# M66_GPRS.net
KiCad netlist of a schematic drawn in Altium Designer
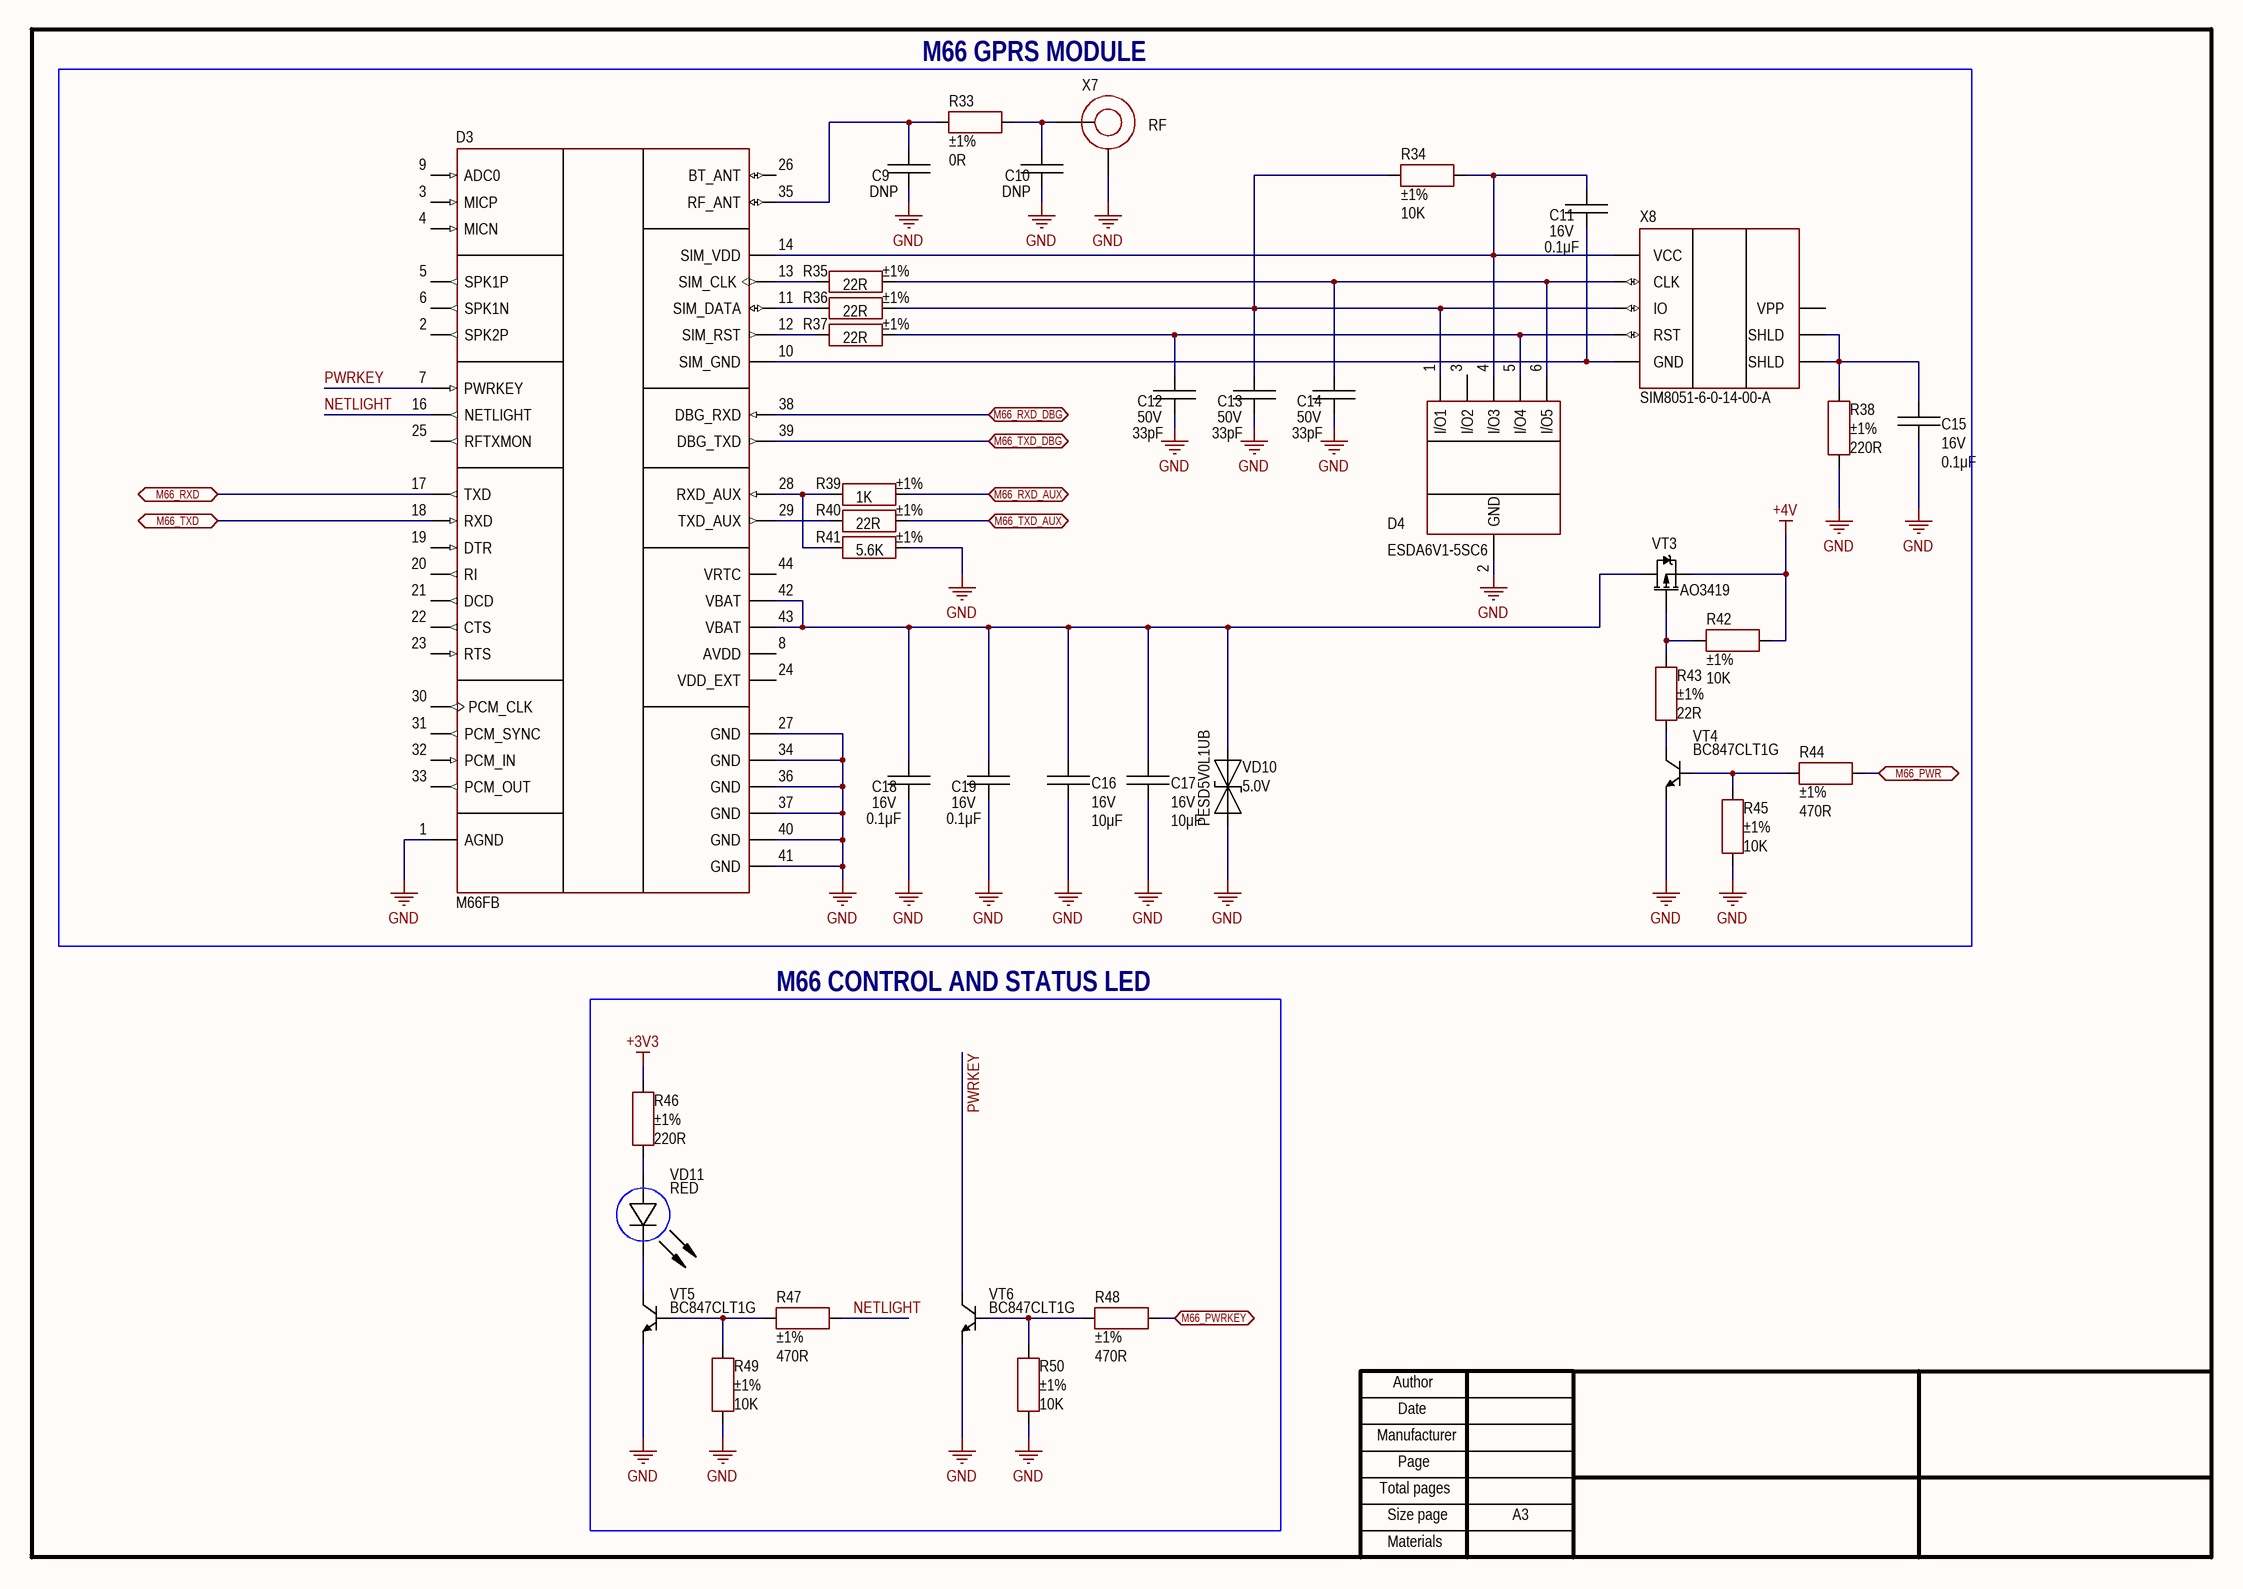
[diagram p0: M66_GPRS.SchDoc]

(export (version "E")
  (design (tool "Eeschema 10.0.6"))
  (components
    (comp (ref "C9")
      (value "DNP")
      (footprint "CAP: 0402")
      (libsource (lib "capacitor") (part "Ceramic_0402"))
    )
    (comp (ref "C10")
      (value "DNP")
      (footprint "CAP: 0402")
      (libsource (lib "capacitor") (part "Ceramic_0402"))
    )
    (comp (ref "C11")
      (value "0.1μF")
      (footprint "CAP: 0402")
      (description "±10% 16V Ceramic Capacitor X7R 0402 (1005 Metric)")
      (fields
        (field (name "MANUFACTURER") "Yageo")
        (field (name "PARTNUMBER") "CC0402KRX7R7BB104")
        (field (name "VOLTAGE") "16V")
      )
      (libsource (lib "capacitor") (part "Ceramic_0402"))
    )
    (comp (ref "C12")
      (value "33pF")
      (footprint "CAP: 0402")
      (description "33 pF ±5% 50V Ceramic Capacitor C0G, NP0 0402 (1005 Metric)")
      (fields
        (field (name "MANUFACTURER") "Yageo")
        (field (name "PARTNUMBER") "CC0402JRNPO9BN330")
        (field (name "VOLTAGE") "50V")
      )
      (libsource (lib "capacitor") (part "Ceramic_0402"))
    )
    (comp (ref "C13")
      (value "33pF")
      (footprint "CAP: 0402")
      (description "33 pF ±5% 50V Ceramic Capacitor C0G, NP0 0402 (1005 Metric)")
      (fields
        (field (name "MANUFACTURER") "Yageo")
        (field (name "PARTNUMBER") "CC0402JRNPO9BN330")
        (field (name "VOLTAGE") "50V")
      )
      (libsource (lib "capacitor") (part "Ceramic_0402"))
    )
    (comp (ref "C14")
      (value "33pF")
      (footprint "CAP: 0402")
      (description "33 pF ±5% 50V Ceramic Capacitor C0G, NP0 0402 (1005 Metric)")
      (fields
        (field (name "MANUFACTURER") "Yageo")
        (field (name "PARTNUMBER") "CC0402JRNPO9BN330")
        (field (name "VOLTAGE") "50V")
      )
      (libsource (lib "capacitor") (part "Ceramic_0402"))
    )
    (comp (ref "C15")
      (value "0.1μF")
      (footprint "CAP: 0402")
      (description "±10% 16V Ceramic Capacitor X7R 0402 (1005 Metric)")
      (fields
        (field (name "MANUFACTURER") "Yageo")
        (field (name "PARTNUMBER") "CC0402KRX7R7BB104")
        (field (name "VOLTAGE") "16V")
      )
      (libsource (lib "capacitor") (part "Ceramic_0402"))
    )
    (comp (ref "C16")
      (value "10μF")
      (footprint "CAP: 0805")
      (description "±20% 16V Ceramic Capacitor X7R 0805 (2012 Metric)")
      (fields
        (field (name "MANUFACTURER") "Yageo")
        (field (name "PARTNUMBER") "CC0805MKX7R7BB106")
        (field (name "VOLTAGE") "16V")
      )
      (libsource (lib "capacitor") (part "Ceramic_0805"))
    )
    (comp (ref "C17")
      (value "10μF")
      (footprint "CAP: 0805")
      (description "±20% 16V Ceramic Capacitor X7R 0805 (2012 Metric)")
      (fields
        (field (name "MANUFACTURER") "Yageo")
        (field (name "PARTNUMBER") "CC0805MKX7R7BB106")
        (field (name "VOLTAGE") "16V")
      )
      (libsource (lib "capacitor") (part "Ceramic_0805"))
    )
    (comp (ref "C18")
      (value "0.1μF")
      (footprint "CAP: 0402")
      (description "±10% 16V Ceramic Capacitor X7R 0402 (1005 Metric)")
      (fields
        (field (name "MANUFACTURER") "Yageo")
        (field (name "PARTNUMBER") "CC0402KRX7R7BB104")
        (field (name "VOLTAGE") "16V")
      )
      (libsource (lib "capacitor") (part "Ceramic_0402"))
    )
    (comp (ref "C19")
      (value "0.1μF")
      (footprint "CAP: 0402")
      (description "±10% 16V Ceramic Capacitor X7R 0402 (1005 Metric)")
      (fields
        (field (name "MANUFACTURER") "Yageo")
        (field (name "PARTNUMBER") "CC0402KRX7R7BB104")
        (field (name "VOLTAGE") "16V")
      )
      (libsource (lib "capacitor") (part "Ceramic_0402"))
    )
    (comp (ref "D3")
      (value "~")
      (footprint "MOD: M66")
      (description "GPRS Modem")
      (fields (field (name "MANUFACTURER") "Quectel") (field (name "PARTNUMBER") "M66FB"))
      (libsource (lib "MyLib") (part "M66FB"))
    )
    (comp (ref "D4")
      (value "~")
      (footprint "SOT23-6")
      (description "6.1V 100W TVS Array Surface Mount SOT-23-6")
      (fields
        (field (name "MANUFACTURER") "STMicroelectronics")
        (field (name "VALUEMANUFACTURERPARTNUMBER") "TVS array, , 5A peak, 6.1V, , SOT-23-6, -40...+125°C")
        (field (name "PARTNUMBER") "ESDA6V1-5SC6")
      )
      (libsource (lib "MyLib") (part "ESDA6V1-5SC6"))
    )
    (comp (ref "R33")
      (value "0R")
      (footprint "RES: 0402")
      (description "0 Ohms Jumper 0.063W, 1/16W Chip Resistor 0402 (1005 Metric) Moisture Resistant Thick Film")
      (fields
        (field (name "MANUFACTURER") "Yageo")
        (field (name "PARTNUMBER") "RC0402JR-070RL")
        (field (name "TOLERANCE") "±1%")
      )
      (libsource (lib "resistor") (part "Resistor_0402"))
    )
    (comp (ref "R34")
      (value "10K")
      (footprint "RES: 0402")
      (description "10 kOhms ±1% 0.063W, 1/16W Chip Resistor 0402 (1005 Metric) Moisture Resistant Thick Film")
      (fields
        (field (name "MANUFACTURER") "Yageo")
        (field (name "PARTNUMBER") "RC0402FR-0710KL")
        (field (name "TOLERANCE") "±1%")
      )
      (libsource (lib "resistor") (part "Resistor_0402"))
    )
    (comp (ref "R35")
      (value "22R")
      (footprint "RES: 0402")
      (description "22 Ohms ±1% 0.063W, 1/16W Chip Resistor 0402 (1005 Metric) Moisture Resistant Thick Film")
      (fields
        (field (name "MANUFACTURER") "Yageo")
        (field (name "PARTNUMBER") "RC0402FR-0722RL")
        (field (name "TOLERANCE") "±1%")
      )
      (libsource (lib "") (part "Resistor_0402_1"))
    )
    (comp (ref "R36")
      (value "22R")
      (footprint "RES: 0402")
      (description "22 Ohms ±1% 0.063W, 1/16W Chip Resistor 0402 (1005 Metric) Moisture Resistant Thick Film")
      (fields
        (field (name "MANUFACTURER") "Yageo")
        (field (name "PARTNUMBER") "RC0402FR-0722RL")
        (field (name "TOLERANCE") "±1%")
      )
      (libsource (lib "") (part "Resistor_0402_1"))
    )
    (comp (ref "R37")
      (value "22R")
      (footprint "RES: 0402")
      (description "22 Ohms ±1% 0.063W, 1/16W Chip Resistor 0402 (1005 Metric) Moisture Resistant Thick Film")
      (fields
        (field (name "MANUFACTURER") "Yageo")
        (field (name "PARTNUMBER") "RC0402FR-0722RL")
        (field (name "TOLERANCE") "±1%")
      )
      (libsource (lib "") (part "Resistor_0402_1"))
    )
    (comp (ref "R38")
      (value "220R")
      (footprint "RES: 0402")
      (description "220 Ohms ±1% 0.063W, 1/16W Chip Resistor 0402 (1005 Metric) Moisture Resistant Thick Film")
      (fields
        (field (name "MANUFACTURER") "Yageo")
        (field (name "PARTNUMBER") "RC0402FR-07220RL")
        (field (name "TOLERANCE") "±1%")
      )
      (libsource (lib "") (part "Resistor_0402_2"))
    )
    (comp (ref "R39")
      (value "1K")
      (footprint "RES: 0402")
      (description "1 kOhms ±1% 0.063W, 1/16W Chip Resistor 0402 (1005 Metric) Moisture Resistant Thick Film")
      (fields
        (field (name "MANUFACTURER") "Yageo")
        (field (name "PARTNUMBER") "RC0402FR-071KP")
        (field (name "TOLERANCE") "±1%")
      )
      (libsource (lib "") (part "Resistor_0402_1"))
    )
    (comp (ref "R40")
      (value "22R")
      (footprint "RES: 0402")
      (description "22 Ohms ±1% 0.063W, 1/16W Chip Resistor 0402 (1005 Metric) Moisture Resistant Thick Film")
      (fields
        (field (name "MANUFACTURER") "Yageo")
        (field (name "PARTNUMBER") "RC0402FR-0722RL")
        (field (name "TOLERANCE") "±1%")
      )
      (libsource (lib "") (part "Resistor_0402_1"))
    )
    (comp (ref "R41")
      (value "5.6K")
      (footprint "RES: 0402")
      (description "5.6 kOhms ±1% 0.063W, 1/16W Chip Resistor 0402 (1005 Metric) Moisture Resistant Thick Film")
      (fields
        (field (name "MANUFACTURER") "Yageo")
        (field (name "PARTNUMBER") "RC0402FR-075K6L")
        (field (name "TOLERANCE") "±1%")
      )
      (libsource (lib "") (part "Resistor_0402_1"))
    )
    (comp (ref "R42")
      (value "10K")
      (footprint "RES: 0402")
      (description "10 kOhms ±1% 0.063W, 1/16W Chip Resistor 0402 (1005 Metric) Moisture Resistant Thick Film")
      (fields
        (field (name "MANUFACTURER") "Yageo")
        (field (name "PARTNUMBER") "RC0402FR-0710KL")
        (field (name "TOLERANCE") "±1%")
      )
      (libsource (lib "resistor") (part "Resistor_0402"))
    )
    (comp (ref "R43")
      (value "22R")
      (footprint "RES: 0402")
      (description "22 Ohms ±1% 0.063W, 1/16W Chip Resistor 0402 (1005 Metric) Moisture Resistant Thick Film")
      (fields
        (field (name "MANUFACTURER") "Yageo")
        (field (name "PARTNUMBER") "RC0402FR-0722RL")
        (field (name "TOLERANCE") "±1%")
      )
      (libsource (lib "") (part "Resistor_0402_2"))
    )
    (comp (ref "R44")
      (value "470R")
      (footprint "RES: 0402")
      (description "470 Ohms ±1% 0.063W, 1/16W Chip Resistor 0402 (1005 Metric) Moisture Resistant Thick Film")
      (fields
        (field (name "MANUFACTURER") "Yageo")
        (field (name "PARTNUMBER") "RC0402FR-07470RL")
        (field (name "TOLERANCE") "±1%")
      )
      (libsource (lib "") (part "Resistor_0402_1"))
    )
    (comp (ref "R45")
      (value "10K")
      (footprint "RES: 0402")
      (description "10 kOhms ±1% 0.063W, 1/16W Chip Resistor 0402 (1005 Metric) Moisture Resistant Thick Film")
      (fields
        (field (name "MANUFACTURER") "Yageo")
        (field (name "PARTNUMBER") "RC0402FR-0710KL")
        (field (name "TOLERANCE") "±1%")
      )
      (libsource (lib "") (part "Resistor_0402_1"))
    )
    (comp (ref "R46")
      (value "220R")
      (footprint "RES: 0402")
      (description "220 Ohms ±1% 0.063W, 1/16W Chip Resistor 0402 (1005 Metric) Moisture Resistant Thick Film")
      (fields
        (field (name "MANUFACTURER") "Yageo")
        (field (name "PARTNUMBER") "RC0402FR-07220RL")
        (field (name "TOLERANCE") "±1%")
      )
      (libsource (lib "") (part "Resistor_0402_2"))
    )
    (comp (ref "R47")
      (value "470R")
      (footprint "RES: 0402")
      (description "470 Ohms ±1% 0.063W, 1/16W Chip Resistor 0402 (1005 Metric) Moisture Resistant Thick Film")
      (fields
        (field (name "MANUFACTURER") "Yageo")
        (field (name "PARTNUMBER") "RC0402FR-07470RL")
        (field (name "TOLERANCE") "±1%")
      )
      (libsource (lib "") (part "Resistor_0402_3"))
    )
    (comp (ref "R48")
      (value "470R")
      (footprint "RES: 0402")
      (description "470 Ohms ±1% 0.063W, 1/16W Chip Resistor 0402 (1005 Metric) Moisture Resistant Thick Film")
      (fields
        (field (name "MANUFACTURER") "Yageo")
        (field (name "PARTNUMBER") "RC0402FR-07470RL")
        (field (name "TOLERANCE") "±1%")
      )
      (libsource (lib "") (part "Resistor_0402_1"))
    )
    (comp (ref "R49")
      (value "10K")
      (footprint "RES: 0402")
      (description "10 kOhms ±1% 0.063W, 1/16W Chip Resistor 0402 (1005 Metric) Moisture Resistant Thick Film")
      (fields
        (field (name "MANUFACTURER") "Yageo")
        (field (name "PARTNUMBER") "RC0402FR-0710KL")
        (field (name "TOLERANCE") "±1%")
      )
      (libsource (lib "") (part "Resistor_0402_1"))
    )
    (comp (ref "R50")
      (value "10K")
      (footprint "RES: 0402")
      (description "10 kOhms ±1% 0.063W, 1/16W Chip Resistor 0402 (1005 Metric) Moisture Resistant Thick Film")
      (fields
        (field (name "MANUFACTURER") "Yageo")
        (field (name "PARTNUMBER") "RC0402FR-0710KL")
        (field (name "TOLERANCE") "±1%")
      )
      (libsource (lib "") (part "Resistor_0402_1"))
    )
    (comp (ref "VD10")
      (value "~")
      (footprint "DIODE: SOD523")
      (description "12V Clamp 3.5A (8/20µs) Ipp Tvs Diode Surface Mount SOD-523")
      (fields
        (field (name "MANUFACTURER") "Nexperia")
        (field (name "VALUEMANUFACTURERPARTNUMBER") "ESD TVS diode, 5.0V, 3.5A, , , SOD-523, -55...+150°C")
        (field (name "VOLTAGE") "5.0V")
        (field (name "PARTNUMBER") "PESD5V0L1UB")
      )
      (libsource (lib "diode") (part "TVS_single"))
    )
    (comp (ref "VD11")
      (value "~")
      (footprint "LED: 0805R")
      (description "Red 625nm LED Indication - Discrete 1.8V 0805 (2012 Metric)")
      (fields
        (field (name "MANUFACTURER") "Kingbright")
        (field (name "VALUEMANUFACTURERPARTNUMBER") "LED, RED, 30mA, 1.8V, 0805, -55...+150°C")
        (field (name "COLOR") "RED")
      )
      (libsource (lib "diode") (part "LED_single"))
    )
    (comp (ref "VT3")
      (value "~")
      (footprint "SOT23")
      (description "P-Channel 20 V 3.5A (Ta) 1.4W (Ta) Surface Mount SOT-23-3")
      (fields
        (field (name "MANUFACTURER") "Alpha & Omega Semiconductor")
        (field (name "VALUEMANUFACTURERPARTNUMBER") "MOSFET P-channel transistor, 20V, 3.5A, 4.4nC, 2.5W, 85mOhm, 400pF, SOT-23-3, -55...+150°C")
        (field (name "PARTNUMBER") "AO3419")
      )
      (libsource (lib "transistor") (part "MOSFET_P_132"))
    )
    (comp (ref "VT4")
      (value "~")
      (footprint "SOT23")
      (description "Bipolar (BJT) Transistor NPN 45 V 100 mA 100MHz 300 mW Surface Mount SOT-23-3 (TO-236)")
      (fields
        (field (name "MANUFACTURER") "ON Semiconductor")
        (field (name "VALUEMANUFACTURERPARTNUMBER") "NPN transistor, 45V, 100mA, 100MHz, 300mW, 0.6V, 420, SOT-23, -55...+125°C")
        (field (name "PARTNUMBER") "BC847CLT1G")
      )
      (libsource (lib "transistor") (part "BJT_NPN_132"))
    )
    (comp (ref "VT5")
      (value "~")
      (footprint "SOT23")
      (description "Bipolar (BJT) Transistor NPN 45 V 100 mA 100MHz 300 mW Surface Mount SOT-23-3 (TO-236)")
      (fields
        (field (name "MANUFACTURER") "ON Semiconductor")
        (field (name "VALUEMANUFACTURERPARTNUMBER") "NPN transistor, 45V, 100mA, 100MHz, 300mW, 0.6V, 420, SOT-23, -55...+125°C")
        (field (name "PARTNUMBER") "BC847CLT1G")
      )
      (libsource (lib "transistor") (part "BJT_NPN_132"))
    )
    (comp (ref "VT6")
      (value "~")
      (footprint "SOT23")
      (description "Bipolar (BJT) Transistor NPN 45 V 100 mA 100MHz 300 mW Surface Mount SOT-23-3 (TO-236)")
      (fields
        (field (name "MANUFACTURER") "ON Semiconductor")
        (field (name "VALUEMANUFACTURERPARTNUMBER") "NPN transistor, 45V, 100mA, 100MHz, 300mW, 0.6V, 420, SOT-23, -55...+125°C")
        (field (name "PARTNUMBER") "BC847CLT1G")
      )
      (libsource (lib "transistor") (part "BJT_NPN_132"))
    )
    (comp (ref "X7")
      (value "~")
      (footprint "CON: u.Fl")
      (description "U.FL (UMCC), AMC Connector Jack, Male Pin 50Ohm Surface Mount Solder")
      (fields
        (field (name "MANUFACTURER") "Amphenol RF")
        (field (name "VALUEMANUFACTURERPARTNUMBER") "Connector u.FL, 50 Ohm, 6GHz")
        (field (name "COMMENTTEXT") "RF")
      )
      (libsource (lib "connector") (part "Connector_uFL"))
    )
    (comp (ref "X8")
      (value "~")
      (footprint "CON: SIM8051-6-0-14-00")
      (description "6 Position Card Connector NANO SIM Surface Mount, Right Angle Gold")
      (fields
        (field (name "MANUFACTURER") "GCT")
        (field (name "VALUEMANUFACTURERPARTNUMBER") "Nano SIM, , , , ")
        (field (name "COMMENTTEXT") "SIM8051-6-0-14-00-A")
      )
      (libsource (lib "MyLib") (part "SIM8051-6-0-14-00-A"))
    )
  )
  (nets
    (net (code "1") (name "+3V3") (class "Default")
      (node (ref "R46") (pin "2") (pinfunction "2_2") (pintype "passive"))
    )
    (net (code "2") (name "+4V") (class "Default")
      (node (ref "R42") (pin "1") (pinfunction "1_1") (pintype "passive"))
      (node (ref "VT3") (pin "2") (pinfunction "S_2") (pintype "passive"))
    )
    (net (code "3") (name "/M66_PWR") (class "Default")
      (node (ref "R44") (pin "2") (pinfunction "2_2") (pintype "passive"))
    )
    (net (code "4") (name "/M66_PWRKEY") (class "Default")
      (node (ref "R48") (pin "2") (pinfunction "2_2") (pintype "passive"))
    )
    (net (code "5") (name "/M66_RXD") (class "Default")
      (node (ref "D3") (pin "17") (pinfunction "TXD_17") (pintype "output"))
    )
    (net (code "6") (name "/M66_RXD_AUX") (class "Default")
      (node (ref "R39") (pin "2") (pinfunction "2_2") (pintype "passive"))
    )
    (net (code "7") (name "/M66_RXD_DBG") (class "Default")
      (node (ref "D3") (pin "38") (pinfunction "DBG_RXD_38") (pintype "input"))
    )
    (net (code "8") (name "/M66_TXD") (class "Default")
      (node (ref "D3") (pin "18") (pinfunction "RXD_18") (pintype "input"))
    )
    (net (code "9") (name "/M66_TXD_AUX") (class "Default")
      (node (ref "R40") (pin "2") (pinfunction "2_2") (pintype "passive"))
    )
    (net (code "10") (name "/M66_TXD_DBG") (class "Default")
      (node (ref "D3") (pin "39") (pinfunction "DBG_TXD_39") (pintype "output"))
    )
    (net (code "11") (name "/NETLIGHT") (class "Default")
      (node (ref "D3") (pin "16") (pinfunction "NETLIGHT_16") (pintype "output"))
      (node (ref "R47") (pin "1") (pinfunction "1_1") (pintype "passive"))
    )
    (net (code "12") (name "/PWRKEY") (class "Default")
      (node (ref "D3") (pin "7") (pinfunction "PWRKEY_7") (pintype "input"))
      (node (ref "VT6") (pin "3") (pinfunction "C_3") (pintype "passive"))
    )
    (net (code "13") (name "GND") (class "Default")
      (node (ref "C10") (pin "2") (pinfunction "2_2") (pintype "passive"))
      (node (ref "C12") (pin "2") (pinfunction "2_2") (pintype "passive"))
      (node (ref "C13") (pin "2") (pinfunction "2_2") (pintype "passive"))
      (node (ref "C14") (pin "2") (pinfunction "2_2") (pintype "passive"))
      (node (ref "C15") (pin "2") (pinfunction "2_2") (pintype "passive"))
      (node (ref "C16") (pin "1") (pinfunction "1_1") (pintype "passive"))
      (node (ref "C17") (pin "1") (pinfunction "1_1") (pintype "passive"))
      (node (ref "C18") (pin "2") (pinfunction "2_2") (pintype "passive"))
      (node (ref "C19") (pin "2") (pinfunction "2_2") (pintype "passive"))
      (node (ref "C9") (pin "2") (pinfunction "2_2") (pintype "passive"))
      (node (ref "D3") (pin "1") (pinfunction "AGND_1") (pintype "power_in"))
      (node (ref "D3") (pin "27") (pinfunction "GND_27") (pintype "power_in"))
      (node (ref "D3") (pin "34") (pinfunction "GND_34") (pintype "power_in"))
      (node (ref "D3") (pin "36") (pinfunction "GND_36") (pintype "power_in"))
      (node (ref "D3") (pin "37") (pinfunction "GND_37") (pintype "power_in"))
      (node (ref "D3") (pin "40") (pinfunction "GND_40") (pintype "power_in"))
      (node (ref "D3") (pin "41") (pinfunction "GND_41") (pintype "power_in"))
      (node (ref "D4") (pin "2") (pinfunction "GND_2") (pintype "passive"))
      (node (ref "R38") (pin "1") (pinfunction "1_1") (pintype "passive"))
      (node (ref "R41") (pin "2") (pinfunction "2_2") (pintype "passive"))
      (node (ref "R45") (pin "1") (pinfunction "1_1") (pintype "passive"))
      (node (ref "R49") (pin "1") (pinfunction "1_1") (pintype "passive"))
      (node (ref "R50") (pin "1") (pinfunction "1_1") (pintype "passive"))
      (node (ref "VD10") (pin "1") (pinfunction "A_1") (pintype "passive"))
      (node (ref "VT4") (pin "2") (pinfunction "E_2") (pintype "passive"))
      (node (ref "VT5") (pin "2") (pinfunction "E_2") (pintype "passive"))
      (node (ref "VT6") (pin "2") (pinfunction "E_2") (pintype "passive"))
      (node (ref "X7") (pin "2") (pinfunction "2_2") (pintype "passive"))
    )
    (net (code "14") (name "Net-(C10-Pad1)") (class "Default")
      (node (ref "C10") (pin "1") (pinfunction "1_1") (pintype "passive"))
      (node (ref "R33") (pin "1") (pinfunction "1_1") (pintype "passive"))
      (node (ref "X7") (pin "1") (pinfunction "1_1") (pintype "passive"))
    )
    (net (code "15") (name "Net-(C15-Pad1)") (class "Default")
      (node (ref "C15") (pin "1") (pinfunction "1_1") (pintype "passive"))
      (node (ref "R38") (pin "2") (pinfunction "2_2") (pintype "passive"))
      (node (ref "X8") (pin "C4") (pinfunction "SHLD_C4") (pintype "passive"))
      (node (ref "X8") (pin "C8") (pinfunction "SHLD_C8") (pintype "passive"))
    )
    (net (code "16") (name "Net-(D3-RF_ANT)") (class "Default")
      (node (ref "C9") (pin "1") (pinfunction "1_1") (pintype "passive"))
      (node (ref "D3") (pin "35") (pinfunction "RF_ANT_35") (pintype "bidirectional"))
      (node (ref "R33") (pin "2") (pinfunction "2_2") (pintype "passive"))
    )
    (net (code "17") (name "Net-(D3-RXD_AUX)") (class "Default")
      (node (ref "D3") (pin "28") (pinfunction "RXD_AUX_28") (pintype "input"))
      (node (ref "R39") (pin "1") (pinfunction "1_1") (pintype "passive"))
      (node (ref "R41") (pin "1") (pinfunction "1_1") (pintype "passive"))
    )
    (net (code "18") (name "Net-(D3-SIM_CLK)") (class "Default")
      (node (ref "D3") (pin "13") (pinfunction "SIM_CLK_13") (pintype "output"))
      (node (ref "R35") (pin "1") (pinfunction "1_1") (pintype "passive"))
    )
    (net (code "19") (name "Net-(D3-SIM_DATA)") (class "Default")
      (node (ref "D3") (pin "11") (pinfunction "SIM_DATA_11") (pintype "bidirectional"))
      (node (ref "R36") (pin "1") (pinfunction "1_1") (pintype "passive"))
    )
    (net (code "20") (name "Net-(D3-SIM_GND)") (class "Default")
      (node (ref "C11") (pin "2") (pinfunction "2_2") (pintype "passive"))
      (node (ref "D3") (pin "10") (pinfunction "SIM_GND_10") (pintype "power_in"))
      (node (ref "X8") (pin "C5") (pinfunction "GND_C5") (pintype "power_in"))
    )
    (net (code "21") (name "Net-(D3-SIM_RST)") (class "Default")
      (node (ref "D3") (pin "12") (pinfunction "SIM_RST_12") (pintype "output"))
      (node (ref "R37") (pin "1") (pinfunction "1_1") (pintype "passive"))
    )
    (net (code "22") (name "Net-(D3-SIM_VDD)") (class "Default")
      (node (ref "C11") (pin "1") (pinfunction "1_1") (pintype "passive"))
      (node (ref "D3") (pin "14") (pinfunction "SIM_VDD_14") (pintype "power_in"))
      (node (ref "D4") (pin "4") (pinfunction "I/O3_4") (pintype "passive"))
      (node (ref "R34") (pin "1") (pinfunction "1_1") (pintype "passive"))
      (node (ref "X8") (pin "C1") (pinfunction "VCC_C1") (pintype "power_in"))
    )
    (net (code "23") (name "Net-(D3-TXD_AUX)") (class "Default")
      (node (ref "D3") (pin "29") (pinfunction "TXD_AUX_29") (pintype "output"))
      (node (ref "R40") (pin "1") (pinfunction "1_1") (pintype "passive"))
    )
    (net (code "24") (name "Net-(D4-I{slash}O1)") (class "Default")
      (node (ref "C13") (pin "1") (pinfunction "1_1") (pintype "passive"))
      (node (ref "D4") (pin "1") (pinfunction "I/O1_1") (pintype "passive"))
      (node (ref "R34") (pin "2") (pinfunction "2_2") (pintype "passive"))
      (node (ref "R36") (pin "2") (pinfunction "2_2") (pintype "passive"))
      (node (ref "X8") (pin "C7") (pinfunction "IO_C7") (pintype "bidirectional"))
    )
    (net (code "25") (name "Net-(D4-I{slash}O4)") (class "Default")
      (node (ref "C12") (pin "1") (pinfunction "1_1") (pintype "passive"))
      (node (ref "D4") (pin "5") (pinfunction "I/O4_5") (pintype "passive"))
      (node (ref "R37") (pin "2") (pinfunction "2_2") (pintype "passive"))
      (node (ref "X8") (pin "C2") (pinfunction "RST_C2") (pintype "bidirectional"))
    )
    (net (code "26") (name "Net-(D4-I{slash}O5)") (class "Default")
      (node (ref "C14") (pin "1") (pinfunction "1_1") (pintype "passive"))
      (node (ref "D4") (pin "6") (pinfunction "I/O5_6") (pintype "passive"))
      (node (ref "R35") (pin "2") (pinfunction "2_2") (pintype "passive"))
      (node (ref "X8") (pin "C3") (pinfunction "CLK_C3") (pintype "bidirectional"))
    )
    (net (code "27") (name "Net-(VD10-C)") (class "Default")
      (node (ref "C16") (pin "2") (pinfunction "2_2") (pintype "passive"))
      (node (ref "C17") (pin "2") (pinfunction "2_2") (pintype "passive"))
      (node (ref "C18") (pin "1") (pinfunction "1_1") (pintype "passive"))
      (node (ref "C19") (pin "1") (pinfunction "1_1") (pintype "passive"))
      (node (ref "D3") (pin "42") (pinfunction "VBAT_42") (pintype "power_in"))
      (node (ref "D3") (pin "43") (pinfunction "VBAT_43") (pintype "power_in"))
      (node (ref "VD10") (pin "2") (pinfunction "C_2") (pintype "passive"))
      (node (ref "VT3") (pin "3") (pinfunction "D_3") (pintype "passive"))
    )
    (net (code "28") (name "Net-(VD11-A)") (class "Default")
      (node (ref "R46") (pin "1") (pinfunction "1_1") (pintype "passive"))
      (node (ref "VD11") (pin "1") (pinfunction "A_1") (pintype "passive"))
    )
    (net (code "29") (name "Net-(VD11-C)") (class "Default")
      (node (ref "VD11") (pin "2") (pinfunction "C_2") (pintype "passive"))
      (node (ref "VT5") (pin "3") (pinfunction "C_3") (pintype "passive"))
    )
    (net (code "30") (name "Net-(VT3-G)") (class "Default")
      (node (ref "R42") (pin "2") (pinfunction "2_2") (pintype "passive"))
      (node (ref "R43") (pin "2") (pinfunction "2_2") (pintype "passive"))
      (node (ref "VT3") (pin "1") (pinfunction "G_1") (pintype "passive"))
    )
    (net (code "31") (name "Net-(VT4-B)") (class "Default")
      (node (ref "R44") (pin "1") (pinfunction "1_1") (pintype "passive"))
      (node (ref "R45") (pin "2") (pinfunction "2_2") (pintype "passive"))
      (node (ref "VT4") (pin "1") (pinfunction "B_1") (pintype "passive"))
    )
    (net (code "32") (name "Net-(VT4-C)") (class "Default")
      (node (ref "R43") (pin "1") (pinfunction "1_1") (pintype "passive"))
      (node (ref "VT4") (pin "3") (pinfunction "C_3") (pintype "passive"))
    )
    (net (code "33") (name "Net-(VT5-B)") (class "Default")
      (node (ref "R47") (pin "2") (pinfunction "2_2") (pintype "passive"))
      (node (ref "R49") (pin "2") (pinfunction "2_2") (pintype "passive"))
      (node (ref "VT5") (pin "1") (pinfunction "B_1") (pintype "passive"))
    )
    (net (code "34") (name "Net-(VT6-B)") (class "Default")
      (node (ref "R48") (pin "1") (pinfunction "1_1") (pintype "passive"))
      (node (ref "R50") (pin "2") (pinfunction "2_2") (pintype "passive"))
      (node (ref "VT6") (pin "1") (pinfunction "B_1") (pintype "passive"))
    )
    (net (code "35") (name "unconnected-(D3-ADC0-Pad9)") (class "Default")
      (node (ref "D3") (pin "9") (pinfunction "ADC0_9") (pintype "input"))
    )
    (net (code "36") (name "unconnected-(D3-AVDD-Pad8)") (class "Default")
      (node (ref "D3") (pin "8") (pinfunction "AVDD_8") (pintype "power_in"))
    )
    (net (code "37") (name "unconnected-(D3-BT_ANT-Pad26)") (class "Default")
      (node (ref "D3") (pin "26") (pinfunction "BT_ANT_26") (pintype "bidirectional"))
    )
    (net (code "38") (name "unconnected-(D3-CTS-Pad22)") (class "Default")
      (node (ref "D3") (pin "22") (pinfunction "CTS_22") (pintype "output"))
    )
    (net (code "39") (name "unconnected-(D3-DCD-Pad21)") (class "Default")
      (node (ref "D3") (pin "21") (pinfunction "DCD_21") (pintype "output"))
    )
    (net (code "40") (name "unconnected-(D3-DTR-Pad19)") (class "Default")
      (node (ref "D3") (pin "19") (pinfunction "DTR_19") (pintype "input"))
    )
    (net (code "41") (name "unconnected-(D3-MICN-Pad4)") (class "Default")
      (node (ref "D3") (pin "4") (pinfunction "MICN_4") (pintype "input"))
    )
    (net (code "42") (name "unconnected-(D3-MICP-Pad3)") (class "Default")
      (node (ref "D3") (pin "3") (pinfunction "MICP_3") (pintype "input"))
    )
    (net (code "43") (name "unconnected-(D3-PCM_CLK-Pad30)") (class "Default")
      (node (ref "D3") (pin "30") (pinfunction "PCM_CLK_30") (pintype "output"))
    )
    (net (code "44") (name "unconnected-(D3-PCM_IN-Pad32)") (class "Default")
      (node (ref "D3") (pin "32") (pinfunction "PCM_IN_32") (pintype "input"))
    )
    (net (code "45") (name "unconnected-(D3-PCM_OUT-Pad33)") (class "Default")
      (node (ref "D3") (pin "33") (pinfunction "PCM_OUT_33") (pintype "output"))
    )
    (net (code "46") (name "unconnected-(D3-PCM_SYNC-Pad31)") (class "Default")
      (node (ref "D3") (pin "31") (pinfunction "PCM_SYNC_31") (pintype "output"))
    )
    (net (code "47") (name "unconnected-(D3-RFTXMON-Pad25)") (class "Default")
      (node (ref "D3") (pin "25") (pinfunction "RFTXMON_25") (pintype "output"))
    )
    (net (code "48") (name "unconnected-(D3-RI-Pad20)") (class "Default")
      (node (ref "D3") (pin "20") (pinfunction "RI_20") (pintype "output"))
    )
    (net (code "49") (name "unconnected-(D3-RTS-Pad23)") (class "Default")
      (node (ref "D3") (pin "23") (pinfunction "RTS_23") (pintype "input"))
    )
    (net (code "50") (name "unconnected-(D3-SPK1N-Pad6)") (class "Default")
      (node (ref "D3") (pin "6") (pinfunction "SPK1N_6") (pintype "output"))
    )
    (net (code "51") (name "unconnected-(D3-SPK1P-Pad5)") (class "Default")
      (node (ref "D3") (pin "5") (pinfunction "SPK1P_5") (pintype "output"))
    )
    (net (code "52") (name "unconnected-(D3-SPK2P-Pad2)") (class "Default")
      (node (ref "D3") (pin "2") (pinfunction "SPK2P_2") (pintype "output"))
    )
    (net (code "53") (name "unconnected-(D3-VDD_EXT-Pad24)") (class "Default")
      (node (ref "D3") (pin "24") (pinfunction "VDD_EXT_24") (pintype "power_in"))
    )
    (net (code "54") (name "unconnected-(D3-VRTC-Pad44)") (class "Default")
      (node (ref "D3") (pin "44") (pinfunction "VRTC_44") (pintype "power_in"))
    )
    (net (code "55") (name "unconnected-(D4-I{slash}O2-Pad3)") (class "Default")
      (node (ref "D4") (pin "3") (pinfunction "I/O2_3") (pintype "passive"))
    )
    (net (code "56") (name "unconnected-(X8-VPP-PadC6)") (class "Default")
      (node (ref "X8") (pin "C6") (pinfunction "VPP_C6") (pintype "power_in"))
    )
  )
)
